# SmartHiveClient_min_V1_0.net
KiCad netlist of a schematic drawn in Altium Designer
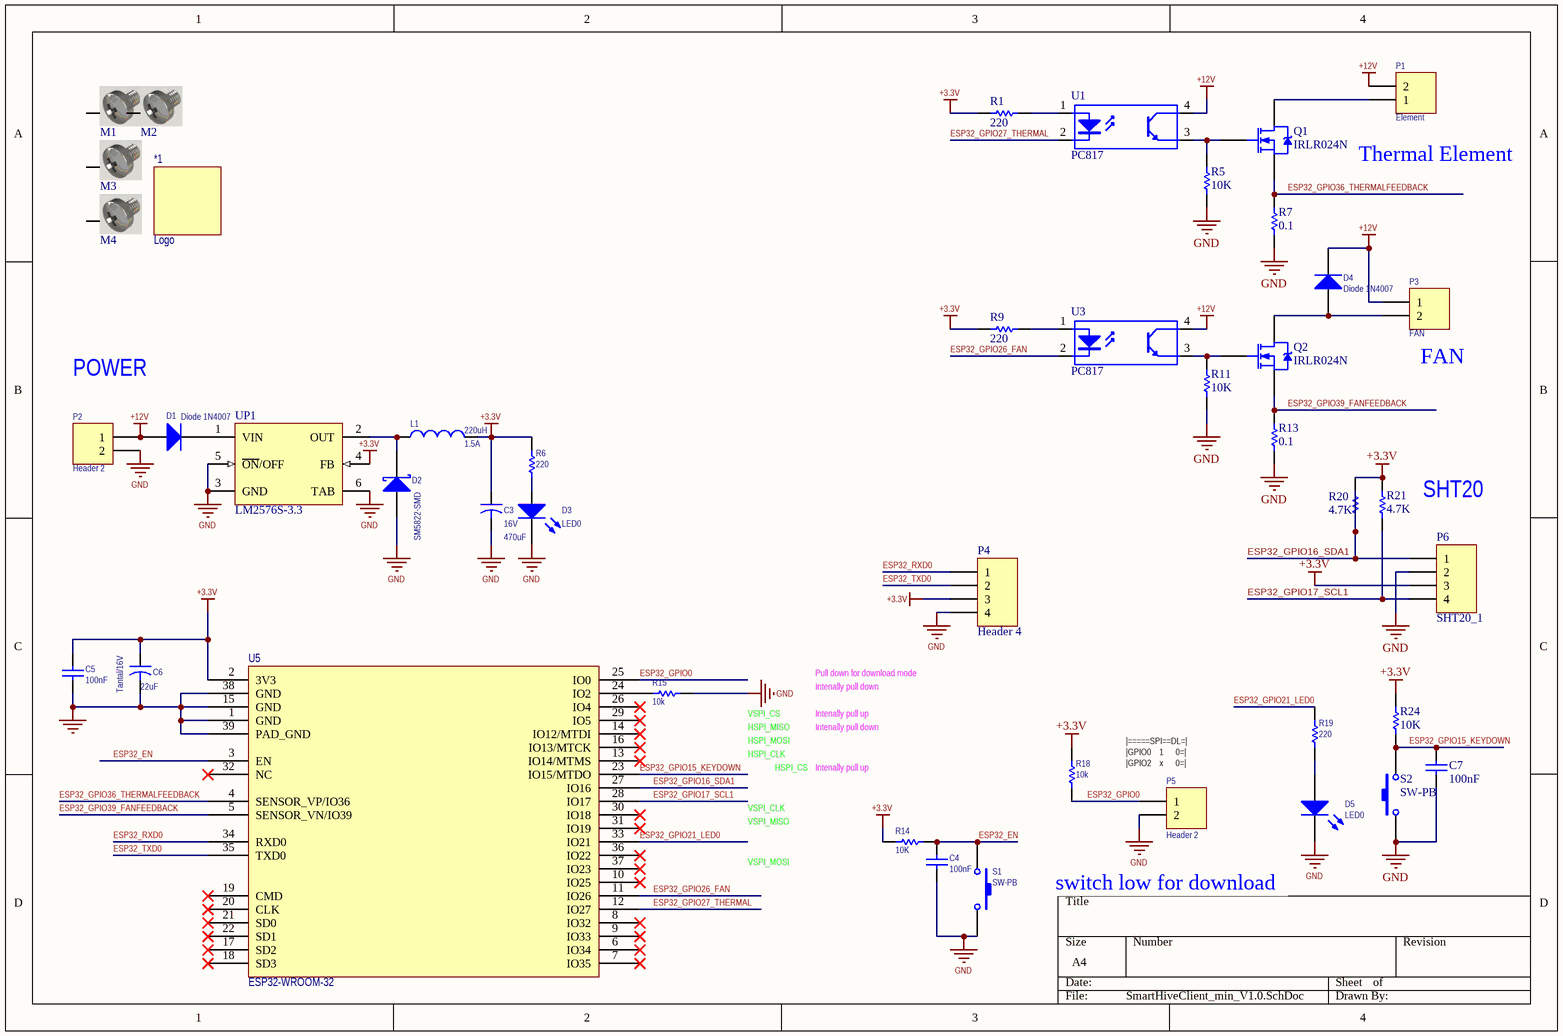
[diagram p0: SmartHiveClient_min_V1.0.SchDoc]

(export (version "E")
  (design (tool "Eeschema 10.0.6"))
  (components
    (comp (ref "*1") (value "Logo") (footprint "LOGO_PARS_TOP") (libsource (lib "Mofidi3D") (part "Logo")))
    (comp (ref "C3")
      (value "16V")
      (footprint "Cap electrolitic radial 8x12-3.5")
      (description "Capacitor")
      (fields (field (name "ALTIUM_VALUE") "470uF") (field (name "PUBLISHER") "Altium Limited"))
      (libsource (lib "Miscellaneous Devices") (part "Cap2"))
    )
    (comp (ref "C4")
      (value "100nF")
      (footprint "CAP0805")
      (description "Capacitor")
      (fields (field (name "PUBLISHER") "Altium Limited"))
      (libsource (lib "Miscellaneous Devices") (part "Cap"))
    )
    (comp (ref "C5")
      (value "100nF")
      (footprint "CAP0805")
      (description "Capacitor")
      (fields (field (name "PUBLISHER") "Altium Limited"))
      (libsource (lib "Miscellaneous Devices") (part "Cap"))
    )
    (comp (ref "C6")
      (value "Tantal/16V")
      (footprint "CAP_TANTAL_TYPE_B")
      (description "Capacitor")
      (fields (field (name "ALTIUM_VALUE") "22uF") (field (name "PUBLISHER") "Altium Limited"))
      (libsource (lib "Miscellaneous Devices") (part "Cap2"))
    )
    (comp (ref "C7")
      (value "100nF")
      (footprint "CAP0805")
      (description "Capacitor")
      (fields (field (name "PUBLISHER") "Altium Limited"))
      (libsource (lib "Miscellaneous Devices") (part "Cap"))
    )
    (comp (ref "D1")
      (value "Diode 1N4007")
      (footprint "DO-241AC")
      (description "1 Amp General Purpose Rectifier")
      (fields (field (name "PUBLISHER") "Altium Limited"))
      (libsource (lib "Miscellaneous Devices") (part "Diode 1N4007"))
    )
    (comp (ref "D2")
      (value "SM5822-SMD")
      (footprint "430X270D")
      (description "Schottky Diode")
      (fields (field (name "PUBLISHER") "Altium Limited"))
      (libsource (lib "Miscellaneous Devices") (part "D Schottky"))
    )
    (comp (ref "D3")
      (value "LED0")
      (footprint "LED_0805")
      (description "Typical INFRARED GaAs LED")
      (fields (field (name "PUBLISHER") "Altium Limited"))
      (libsource (lib "Miscellaneous Devices") (part "LED0"))
    )
    (comp (ref "D4")
      (value "Diode 1N4007")
      (footprint "DO-241AC")
      (description "1 Amp General Purpose Rectifier")
      (fields (field (name "PUBLISHER") "Altium Limited"))
      (libsource (lib "Miscellaneous Devices") (part "Diode 1N4007"))
    )
    (comp (ref "D5")
      (value "LED0")
      (footprint "LED_0805")
      (description "Typical INFRARED GaAs LED")
      (fields (field (name "PUBLISHER") "Altium Limited"))
      (libsource (lib "Miscellaneous Devices") (part "LED0"))
    )
    (comp (ref "L1")
      (value "1.5A")
      (footprint "Inductor SMD 3x3.2mm")
      (description "Inductor")
      (fields (field (name "ALTIUM_VALUE") "220uH") (field (name "PUBLISHER") "Altium Limited"))
      (libsource (lib "Miscellaneous Devices") (part "Inductor"))
    )
    (comp (ref "M1")
      (value "Screw3mm")
      (footprint "Board Screw 3mm")
      (description "Board Screw With Spacer 3mm")
      (fields (field (name "DESIGNER") "Abbas Basereh"))
      (libsource (lib "Mofidi3D") (part "Board Screw 3mm"))
    )
    (comp (ref "M2")
      (value "Screw3mm")
      (footprint "Board Screw 3mm")
      (description "Board Screw With Spacer 3mm")
      (fields (field (name "DESIGNER") "Abbas Basereh"))
      (libsource (lib "Mofidi3D") (part "Board Screw 3mm"))
    )
    (comp (ref "M3")
      (value "Screw3mm")
      (footprint "Board Screw 3mm")
      (description "Board Screw With Spacer 3mm")
      (fields (field (name "DESIGNER") "Abbas Basereh"))
      (libsource (lib "Mofidi3D") (part "Board Screw 3mm"))
    )
    (comp (ref "M4")
      (value "Screw3mm")
      (footprint "Board Screw 3mm")
      (description "Board Screw With Spacer 3mm")
      (fields (field (name "DESIGNER") "Abbas Basereh"))
      (libsource (lib "Mofidi3D") (part "Board Screw 3mm"))
    )
    (comp (ref "P1")
      (value "Element")
      (footprint "MSTBV 2,5/2-G-5")
      (description "Header, 2-Pin")
      (fields (field (name "PUBLISHER") "Altium Limited"))
      (libsource (lib "") (part "Header 2_2"))
    )
    (comp (ref "P2")
      (value "Header 2")
      (footprint "KF301 2PIN")
      (description "Header, 2-Pin")
      (fields (field (name "PUBLISHER") "Altium Limited"))
      (libsource (lib "") (part "Header 2_1"))
    )
    (comp (ref "P3")
      (value "FAN")
      (footprint "DS1070-2-COMCON")
      (description "Header, 2-Pin")
      (fields (field (name "PUBLISHER") "Altium Limited"))
      (libsource (lib "Miscellaneous Connectors") (part "Header 2"))
    )
    (comp (ref "P4")
      (value "Header 4")
      (footprint "HDR1X4")
      (description "Header, 4-Pin")
      (fields (field (name "PUBLISHER") "Altium Limited"))
      (libsource (lib "Miscellaneous Connectors") (part "Header 4"))
    )
    (comp (ref "P5")
      (value "Header 2")
      (footprint "Jumper Small - 2.54 - Black")
      (description "Header, 2-Pin")
      (fields (field (name "PUBLISHER") "Altium Limited"))
      (libsource (lib "Miscellaneous Connectors") (part "Header 2"))
    )
    (comp (ref "P6")
      (value "SHT20_1")
      (footprint "XH-4PIN")
      (description "Header, 4-Pin")
      (fields (field (name "PUBLISHER") "Altium Limited"))
      (libsource (lib "Miscellaneous Connectors") (part "Header 4"))
    )
    (comp (ref "Q1")
      (value "IRLR024N")
      (footprint "TO252-3M")
      (description "HEXFET Power MOSFET")
      (fields (field (name "PUBLISHER") "Altium Limited"))
      (libsource (lib "IR Discrete MOSFET - Power") (part "IRLR024N"))
    )
    (comp (ref "Q2")
      (value "IRLR024N")
      (footprint "TO252-3M")
      (description "HEXFET Power MOSFET")
      (fields (field (name "PUBLISHER") "Altium Limited"))
      (libsource (lib "IR Discrete MOSFET - Power") (part "IRLR024N"))
    )
    (comp (ref "R1")
      (value "220")
      (footprint "RES0805")
      (description "Resistor")
      (fields (field (name "PUBLISHER") "Altium Limited"))
      (libsource (lib "Miscellaneous Devices") (part "Res1"))
    )
    (comp (ref "R5")
      (value "10K")
      (footprint "RES0805")
      (description "Resistor")
      (fields (field (name "PUBLISHER") "Altium Limited"))
      (libsource (lib "Miscellaneous Devices") (part "Res1"))
    )
    (comp (ref "R6")
      (value "220")
      (footprint "RES0805")
      (description "Resistor")
      (fields (field (name "PUBLISHER") "Altium Limited"))
      (libsource (lib "Miscellaneous Devices") (part "Res1"))
    )
    (comp (ref "R7")
      (value "0.1")
      (footprint "RES2512")
      (description "Size:2512,1%")
      (fields (field (name "PUBLISHER") "Altium Limited"))
      (libsource (lib "Miscellaneous Devices") (part "Res1"))
    )
    (comp (ref "R9")
      (value "220")
      (footprint "RES0805")
      (description "Resistor")
      (fields (field (name "PUBLISHER") "Altium Limited"))
      (libsource (lib "Miscellaneous Devices") (part "Res1"))
    )
    (comp (ref "R11")
      (value "10K")
      (footprint "RES0805")
      (description "Resistor")
      (fields (field (name "PUBLISHER") "Altium Limited"))
      (libsource (lib "Miscellaneous Devices") (part "Res1"))
    )
    (comp (ref "R13")
      (value "0.1")
      (footprint "RES2512")
      (description "Size:2512,1%")
      (fields (field (name "PUBLISHER") "Altium Limited"))
      (libsource (lib "Miscellaneous Devices") (part "Res1"))
    )
    (comp (ref "R14")
      (value "10K")
      (footprint "RES0805")
      (description "Resistor")
      (fields (field (name "PUBLISHER") "Altium Limited"))
      (libsource (lib "Miscellaneous Devices") (part "Res1"))
    )
    (comp (ref "R15")
      (value "10k")
      (footprint "RES0805")
      (description "Resistor")
      (fields (field (name "PUBLISHER") "Altium Limited"))
      (libsource (lib "Miscellaneous Devices") (part "Res1"))
    )
    (comp (ref "R18")
      (value "10k")
      (footprint "RES0805")
      (description "Resistor")
      (fields (field (name "PUBLISHER") "Altium Limited"))
      (libsource (lib "Miscellaneous Devices") (part "Res1"))
    )
    (comp (ref "R19")
      (value "220")
      (footprint "RES0805")
      (description "Resistor")
      (fields (field (name "PUBLISHER") "Altium Limited"))
      (libsource (lib "Miscellaneous Devices") (part "Res1"))
    )
    (comp (ref "R20")
      (value "4.7K")
      (footprint "RES0805")
      (description "Resistor")
      (fields (field (name "PUBLISHER") "Altium Limited"))
      (libsource (lib "Miscellaneous Devices") (part "Res1"))
    )
    (comp (ref "R21")
      (value "4.7K")
      (footprint "RES0805")
      (description "Resistor")
      (fields (field (name "PUBLISHER") "Altium Limited"))
      (libsource (lib "Miscellaneous Devices") (part "Res1"))
    )
    (comp (ref "R24")
      (value "10K")
      (footprint "RES0805")
      (description "Resistor")
      (fields (field (name "PUBLISHER") "Altium Limited"))
      (libsource (lib "Miscellaneous Devices") (part "Res1"))
    )
    (comp (ref "S1")
      (value "SW-PB")
      (footprint "SW-2PIN-SMD")
      (description "Switch")
      (fields (field (name "PUBLISHER") "Altium Limited"))
      (libsource (lib "Miscellaneous Devices") (part "SW-PB"))
    )
    (comp (ref "S2")
      (value "SW-PB")
      (footprint "SW-2PIN-SMD")
      (description "Switch")
      (fields (field (name "PUBLISHER") "Altium Limited"))
      (libsource (lib "Miscellaneous Devices") (part "SW-PB"))
    )
    (comp (ref "U1")
      (value "PC817")
      (footprint "DIP_4")
      (description "4-Pin Phototransistor Optocoupler")
      (fields (field (name "PUBLISHER") "Altium Limited"))
      (libsource (lib "Miscellaneous Devices") (part "Optoisolator1"))
    )
    (comp (ref "U3")
      (value "PC817")
      (footprint "DIP_4")
      (description "4-Pin Phototransistor Optocoupler")
      (fields (field (name "PUBLISHER") "Altium Limited"))
      (libsource (lib "Miscellaneous Devices") (part "Optoisolator1"))
    )
    (comp (ref "U5")
      (value "ESP32-WROOM-32")
      (footprint "ESP32-WROOM-32D")
      (description "ESP32  a single chip 2.4 GHz Wi-Fi and Bluetooth combo chip")
      (libsource (lib "Mofidi3D") (part "ESP32-WROOM-32"))
    )
    (comp (ref "UP1")
      (value "LM2576S-3.3")
      (footprint "TO263")
      (description "SIMPLE SWITCHER® 3A Step-Down Voltage Regulator, 5-pin TO-263")
      (fields
        (field (name "MANUFACTURER") "National Semiconductor")
        (field (name "PUBLISHER") "Altium Limited")
      )
      (libsource (lib "NSC Switcher") (part "LM2576S-3.3"))
    )
  )
  (nets
    (net (code "1") (name "+3.3V") (class "Default")
      (node (ref "C3") (pin "1") (pinfunction "1_1") (pintype "passive"))
      (node (ref "C5") (pin "2") (pinfunction "2_2") (pintype "passive"))
      (node (ref "C6") (pin "1") (pinfunction "1_1") (pintype "passive"))
      (node (ref "L1") (pin "2") (pinfunction "2_2") (pintype "passive"))
      (node (ref "P4") (pin "3") (pinfunction "3_3") (pintype "passive"))
      (node (ref "P6") (pin "3") (pinfunction "3_3") (pintype "passive"))
      (node (ref "R1") (pin "1") (pinfunction "1_1") (pintype "passive"))
      (node (ref "R14") (pin "2") (pinfunction "2_2") (pintype "passive"))
      (node (ref "R18") (pin "2") (pinfunction "2_2") (pintype "passive"))
      (node (ref "R20") (pin "2") (pinfunction "2_2") (pintype "passive"))
      (node (ref "R21") (pin "2") (pinfunction "2_2") (pintype "passive"))
      (node (ref "R24") (pin "2") (pinfunction "2_2") (pintype "passive"))
      (node (ref "R6") (pin "2") (pinfunction "2_2") (pintype "passive"))
      (node (ref "R9") (pin "1") (pinfunction "1_1") (pintype "passive"))
      (node (ref "U5") (pin "2") (pinfunction "3V3_2") (pintype "power_in"))
      (node (ref "UP1") (pin "4") (pinfunction "FB_4") (pintype "input"))
    )
    (net (code "2") (name "+12V") (class "Default")
      (node (ref "D1") (pin "1") (pinfunction "A_1") (pintype "passive"))
      (node (ref "D4") (pin "2") (pinfunction "K_2") (pintype "passive"))
      (node (ref "P1") (pin "2") (pinfunction "2_2") (pintype "passive"))
      (node (ref "P2") (pin "1") (pinfunction "1_1") (pintype "passive"))
      (node (ref "P3") (pin "1") (pinfunction "1_1") (pintype "passive"))
      (node (ref "U1") (pin "4") (pinfunction "C_4") (pintype "passive"))
      (node (ref "U3") (pin "4") (pinfunction "C_4") (pintype "passive"))
    )
    (net (code "3") (name "/ESP32_EN") (class "Default")
      (node (ref "C4") (pin "2") (pinfunction "2_2") (pintype "passive"))
      (node (ref "R14") (pin "1") (pinfunction "1_1") (pintype "passive"))
      (node (ref "S1") (pin "1") (pinfunction "1_1") (pintype "passive"))
      (node (ref "U5") (pin "3") (pinfunction "EN_3") (pintype "passive"))
    )
    (net (code "4") (name "/ESP32_GPIO0") (class "Default")
      (node (ref "P5") (pin "1") (pinfunction "1_1") (pintype "passive"))
      (node (ref "R18") (pin "1") (pinfunction "1_1") (pintype "passive"))
      (node (ref "U5") (pin "25") (pinfunction "IO0_25") (pintype "passive"))
    )
    (net (code "5") (name "/ESP32_GPIO15_KEYDOWN") (class "Default")
      (node (ref "C7") (pin "2") (pinfunction "2_2") (pintype "passive"))
      (node (ref "R24") (pin "1") (pinfunction "1_1") (pintype "passive"))
      (node (ref "S2") (pin "1") (pinfunction "1_1") (pintype "passive"))
      (node (ref "U5") (pin "23") (pinfunction "IO15/MTDO_23") (pintype "passive"))
    )
    (net (code "6") (name "/ESP32_GPIO16_SDA1") (class "Default")
      (node (ref "P6") (pin "1") (pinfunction "1_1") (pintype "passive"))
      (node (ref "R20") (pin "1") (pinfunction "1_1") (pintype "passive"))
      (node (ref "U5") (pin "27") (pinfunction "IO16_27") (pintype "passive"))
    )
    (net (code "7") (name "/ESP32_GPIO17_SCL1") (class "Default")
      (node (ref "P6") (pin "4") (pinfunction "4_4") (pintype "passive"))
      (node (ref "R21") (pin "1") (pinfunction "1_1") (pintype "passive"))
      (node (ref "U5") (pin "28") (pinfunction "IO17_28") (pintype "passive"))
    )
    (net (code "8") (name "/ESP32_GPIO21_LED0") (class "Default")
      (node (ref "R19") (pin "1") (pinfunction "1_1") (pintype "passive"))
      (node (ref "U5") (pin "33") (pinfunction "IO21_33") (pintype "passive"))
    )
    (net (code "9") (name "/ESP32_GPIO26_FAN") (class "Default")
      (node (ref "U3") (pin "2") (pinfunction "K_2") (pintype "passive"))
      (node (ref "U5") (pin "11") (pinfunction "IO26_11") (pintype "passive"))
    )
    (net (code "10") (name "/ESP32_GPIO27_THERMAL") (class "Default")
      (node (ref "U1") (pin "2") (pinfunction "K_2") (pintype "passive"))
      (node (ref "U5") (pin "12") (pinfunction "IO27_12") (pintype "passive"))
    )
    (net (code "11") (name "/ESP32_GPIO36_THERMALFEEDBACK") (class "Default")
      (node (ref "Q1") (pin "3") (pinfunction "S_3") (pintype "passive"))
      (node (ref "R7") (pin "2") (pinfunction "2_2") (pintype "passive"))
      (node (ref "U5") (pin "4") (pinfunction "SENSOR_VP/IO36_4") (pintype "passive"))
    )
    (net (code "12") (name "/ESP32_GPIO39_FANFEEDBACK") (class "Default")
      (node (ref "Q2") (pin "3") (pinfunction "S_3") (pintype "passive"))
      (node (ref "R13") (pin "2") (pinfunction "2_2") (pintype "passive"))
      (node (ref "U5") (pin "5") (pinfunction "SENSOR_VN/IO39_5") (pintype "passive"))
    )
    (net (code "13") (name "/ESP32_RXD0") (class "Default")
      (node (ref "P4") (pin "1") (pinfunction "1_1") (pintype "passive"))
      (node (ref "U5") (pin "34") (pinfunction "RXD0_34") (pintype "passive"))
    )
    (net (code "14") (name "/ESP32_TXD0") (class "Default")
      (node (ref "P4") (pin "2") (pinfunction "2_2") (pintype "passive"))
      (node (ref "U5") (pin "35") (pinfunction "TXD0_35") (pintype "passive"))
    )
    (net (code "15") (name "GND") (class "Default")
      (node (ref "C3") (pin "2") (pinfunction "2_2") (pintype "passive"))
      (node (ref "C4") (pin "1") (pinfunction "1_1") (pintype "passive"))
      (node (ref "C5") (pin "1") (pinfunction "1_1") (pintype "passive"))
      (node (ref "C6") (pin "2") (pinfunction "2_2") (pintype "passive"))
      (node (ref "C7") (pin "1") (pinfunction "1_1") (pintype "passive"))
      (node (ref "D2") (pin "1") (pinfunction "A_1") (pintype "passive"))
      (node (ref "D3") (pin "2") (pinfunction "K_2") (pintype "passive"))
      (node (ref "D5") (pin "2") (pinfunction "K_2") (pintype "passive"))
      (node (ref "P2") (pin "2") (pinfunction "2_2") (pintype "passive"))
      (node (ref "P4") (pin "4") (pinfunction "4_4") (pintype "passive"))
      (node (ref "P5") (pin "2") (pinfunction "2_2") (pintype "passive"))
      (node (ref "P6") (pin "2") (pinfunction "2_2") (pintype "passive"))
      (node (ref "R11") (pin "1") (pinfunction "1_1") (pintype "passive"))
      (node (ref "R13") (pin "1") (pinfunction "1_1") (pintype "passive"))
      (node (ref "R15") (pin "1") (pinfunction "1_1") (pintype "passive"))
      (node (ref "R5") (pin "1") (pinfunction "1_1") (pintype "passive"))
      (node (ref "R7") (pin "1") (pinfunction "1_1") (pintype "passive"))
      (node (ref "S1") (pin "2") (pinfunction "2_2") (pintype "passive"))
      (node (ref "S2") (pin "2") (pinfunction "2_2") (pintype "passive"))
      (node (ref "U5") (pin "1") (pinfunction "GND_1") (pintype "power_in"))
      (node (ref "U5") (pin "15") (pinfunction "GND_15") (pintype "power_in"))
      (node (ref "U5") (pin "38") (pinfunction "GND_38") (pintype "power_in"))
      (node (ref "U5") (pin "39") (pinfunction "PAD_GND_39") (pintype "passive"))
      (node (ref "UP1") (pin "3") (pinfunction "GND_3") (pintype "power_in"))
      (node (ref "UP1") (pin "5") (pinfunction "~{ON}/OFF_5") (pintype "input"))
      (node (ref "UP1") (pin "6") (pinfunction "TAB_6") (pintype "power_in"))
    )
    (net (code "16") (name "Net-(D1-K)") (class "Default")
      (node (ref "D1") (pin "2") (pinfunction "K_2") (pintype "passive"))
      (node (ref "UP1") (pin "1") (pinfunction "VIN_1") (pintype "power_in"))
    )
    (net (code "17") (name "Net-(D2-K)") (class "Default")
      (node (ref "D2") (pin "2") (pinfunction "K_2") (pintype "passive"))
      (node (ref "L1") (pin "1") (pinfunction "1_1") (pintype "passive"))
      (node (ref "UP1") (pin "2") (pinfunction "OUT_2") (pintype "power_in"))
    )
    (net (code "18") (name "Net-(D3-A)") (class "Default")
      (node (ref "D3") (pin "1") (pinfunction "A_1") (pintype "passive"))
      (node (ref "R6") (pin "1") (pinfunction "1_1") (pintype "passive"))
    )
    (net (code "19") (name "Net-(D4-A)") (class "Default")
      (node (ref "D4") (pin "1") (pinfunction "A_1") (pintype "passive"))
      (node (ref "P3") (pin "2") (pinfunction "2_2") (pintype "passive"))
      (node (ref "Q2") (pin "4") (pinfunction "D_4") (pintype "passive"))
    )
    (net (code "20") (name "Net-(D5-A)") (class "Default")
      (node (ref "D5") (pin "1") (pinfunction "A_1") (pintype "passive"))
      (node (ref "R19") (pin "2") (pinfunction "2_2") (pintype "passive"))
    )
    (net (code "21") (name "Net-(Q1-D)") (class "Default")
      (node (ref "P1") (pin "1") (pinfunction "1_1") (pintype "passive"))
      (node (ref "Q1") (pin "4") (pinfunction "D_4") (pintype "passive"))
    )
    (net (code "22") (name "Net-(Q1-G)") (class "Default")
      (node (ref "Q1") (pin "1") (pinfunction "G_1") (pintype "passive"))
      (node (ref "R5") (pin "2") (pinfunction "2_2") (pintype "passive"))
      (node (ref "U1") (pin "3") (pinfunction "E_3") (pintype "passive"))
    )
    (net (code "23") (name "Net-(Q2-G)") (class "Default")
      (node (ref "Q2") (pin "1") (pinfunction "G_1") (pintype "passive"))
      (node (ref "R11") (pin "2") (pinfunction "2_2") (pintype "passive"))
      (node (ref "U3") (pin "3") (pinfunction "E_3") (pintype "passive"))
    )
    (net (code "24") (name "Net-(U1-A)") (class "Default")
      (node (ref "R1") (pin "2") (pinfunction "2_2") (pintype "passive"))
      (node (ref "U1") (pin "1") (pinfunction "A_1") (pintype "passive"))
    )
    (net (code "25") (name "Net-(U3-A)") (class "Default")
      (node (ref "R9") (pin "2") (pinfunction "2_2") (pintype "passive"))
      (node (ref "U3") (pin "1") (pinfunction "A_1") (pintype "passive"))
    )
    (net (code "26") (name "Net-(U5-IO2)") (class "Default")
      (node (ref "R15") (pin "2") (pinfunction "2_2") (pintype "passive"))
      (node (ref "U5") (pin "24") (pinfunction "IO2_24") (pintype "passive"))
    )
    (net (code "27") (name "unconnected-(M1-PadS)") (class "Default")
      (node (ref "M1") (pin "S") (pinfunction "S_S") (pintype "passive"))
    )
    (net (code "28") (name "unconnected-(M2-PadS)") (class "Default")
      (node (ref "M2") (pin "S") (pinfunction "S_S") (pintype "passive"))
    )
    (net (code "29") (name "unconnected-(M3-PadS)") (class "Default")
      (node (ref "M3") (pin "S") (pinfunction "S_S") (pintype "passive"))
    )
    (net (code "30") (name "unconnected-(M4-PadS)") (class "Default")
      (node (ref "M4") (pin "S") (pinfunction "S_S") (pintype "passive"))
    )
    (net (code "31") (name "unconnected-(U5-CLK-Pad20)") (class "Default")
      (node (ref "U5") (pin "20") (pinfunction "CLK_20") (pintype "passive+no_connect"))
    )
    (net (code "32") (name "unconnected-(U5-CMD-Pad19)") (class "Default")
      (node (ref "U5") (pin "19") (pinfunction "CMD_19") (pintype "passive+no_connect"))
    )
    (net (code "33") (name "unconnected-(U5-IO4-Pad26)") (class "Default")
      (node (ref "U5") (pin "26") (pinfunction "IO4_26") (pintype "passive+no_connect"))
    )
    (net (code "34") (name "unconnected-(U5-IO5-Pad29)") (class "Default")
      (node (ref "U5") (pin "29") (pinfunction "IO5_29") (pintype "passive+no_connect"))
    )
    (net (code "35") (name "unconnected-(U5-IO12{slash}MTDI-Pad14)") (class "Default")
      (node (ref "U5") (pin "14") (pinfunction "IO12/MTDI_14") (pintype "passive+no_connect"))
    )
    (net (code "36") (name "unconnected-(U5-IO13{slash}MTCK-Pad16)") (class "Default")
      (node (ref "U5") (pin "16") (pinfunction "IO13/MTCK_16") (pintype "passive+no_connect"))
    )
    (net (code "37") (name "unconnected-(U5-IO14{slash}MTMS-Pad13)") (class "Default")
      (node (ref "U5") (pin "13") (pinfunction "IO14/MTMS_13") (pintype "passive+no_connect"))
    )
    (net (code "38") (name "unconnected-(U5-IO18-Pad30)") (class "Default")
      (node (ref "U5") (pin "30") (pinfunction "IO18_30") (pintype "passive+no_connect"))
    )
    (net (code "39") (name "unconnected-(U5-IO19-Pad31)") (class "Default")
      (node (ref "U5") (pin "31") (pinfunction "IO19_31") (pintype "passive+no_connect"))
    )
    (net (code "40") (name "unconnected-(U5-IO22-Pad36)") (class "Default")
      (node (ref "U5") (pin "36") (pinfunction "IO22_36") (pintype "passive+no_connect"))
    )
    (net (code "41") (name "unconnected-(U5-IO23-Pad37)") (class "Default")
      (node (ref "U5") (pin "37") (pinfunction "IO23_37") (pintype "passive+no_connect"))
    )
    (net (code "42") (name "unconnected-(U5-IO25-Pad10)") (class "Default")
      (node (ref "U5") (pin "10") (pinfunction "IO25_10") (pintype "passive+no_connect"))
    )
    (net (code "43") (name "unconnected-(U5-IO32-Pad8)") (class "Default")
      (node (ref "U5") (pin "8") (pinfunction "IO32_8") (pintype "passive+no_connect"))
    )
    (net (code "44") (name "unconnected-(U5-IO33-Pad9)") (class "Default")
      (node (ref "U5") (pin "9") (pinfunction "IO33_9") (pintype "passive+no_connect"))
    )
    (net (code "45") (name "unconnected-(U5-IO34-Pad6)") (class "Default")
      (node (ref "U5") (pin "6") (pinfunction "IO34_6") (pintype "passive+no_connect"))
    )
    (net (code "46") (name "unconnected-(U5-IO35-Pad7)") (class "Default")
      (node (ref "U5") (pin "7") (pinfunction "IO35_7") (pintype "passive+no_connect"))
    )
    (net (code "47") (name "unconnected-(U5-NC-Pad32)") (class "Default")
      (node (ref "U5") (pin "32") (pinfunction "NC_32") (pintype "passive+no_connect"))
    )
    (net (code "48") (name "unconnected-(U5-SD0-Pad21)") (class "Default")
      (node (ref "U5") (pin "21") (pinfunction "SD0_21") (pintype "passive+no_connect"))
    )
    (net (code "49") (name "unconnected-(U5-SD1-Pad22)") (class "Default")
      (node (ref "U5") (pin "22") (pinfunction "SD1_22") (pintype "passive+no_connect"))
    )
    (net (code "50") (name "unconnected-(U5-SD2-Pad17)") (class "Default")
      (node (ref "U5") (pin "17") (pinfunction "SD2_17") (pintype "passive+no_connect"))
    )
    (net (code "51") (name "unconnected-(U5-SD3-Pad18)") (class "Default")
      (node (ref "U5") (pin "18") (pinfunction "SD3_18") (pintype "passive+no_connect"))
    )
  )
)
